# HARTShield.net
KiCad netlist of a schematic drawn in EAGLE
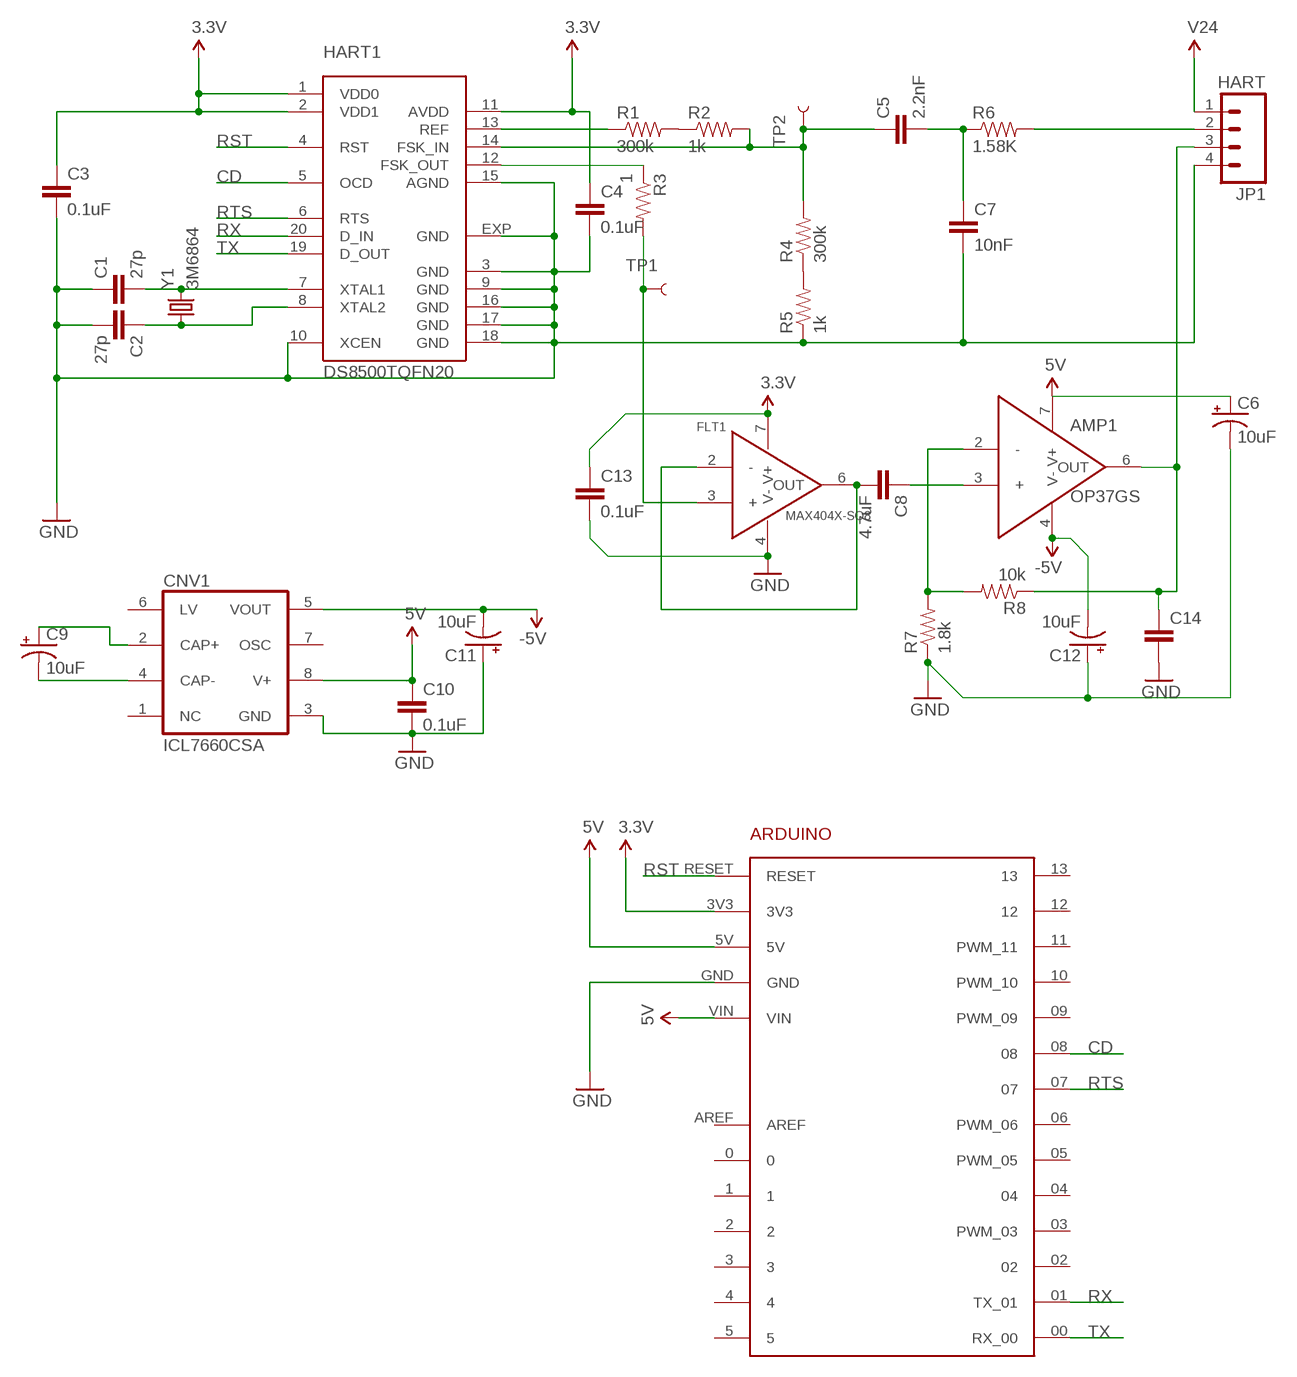
[diagram p0: schematic, sheet 1]

(export (version "E")
  (design (tool "Eeschema 10.0.6"))
  (components
    (comp (ref "AMP1")
      (value "OP37GS")
      (footprint "eagle-import:SO8")
      (libsource (lib "eagle-import") (part "OP37GS"))
    )
    (comp (ref "ARDUINO1")
      (value "ARDUINO")
      (footprint "eagle-import:ARDUINO")
      (libsource (lib "eagle-import") (part "ARDUINO"))
    )
    (comp (ref "C1")
      (value "27p")
      (footprint "eagle-import:0603-CAP")
      (libsource (lib "eagle-import") (part "CAP0603-CAP"))
    )
    (comp (ref "C2")
      (value "27p")
      (footprint "eagle-import:0603-CAP")
      (libsource (lib "eagle-import") (part "CAP0603-CAP"))
    )
    (comp (ref "C3")
      (value "0.1uF")
      (footprint "eagle-import:0603-CAP")
      (libsource (lib "eagle-import") (part "0.1UF-25V(+80/-20%)(0603)"))
    )
    (comp (ref "C4")
      (value "0.1uF")
      (footprint "eagle-import:0603-CAP")
      (libsource (lib "eagle-import") (part "0.1UF-25V(+80/-20%)(0603)"))
    )
    (comp (ref "C5")
      (value "2.2nF")
      (footprint "eagle-import:0603-CAP")
      (libsource (lib "eagle-import") (part "0.1UF-25V(+80/-20%)(0603)"))
    )
    (comp (ref "C6")
      (value "10uF")
      (footprint "eagle-import:EIA3216")
      (libsource (lib "eagle-import") (part "10UF-TANT"))
    )
    (comp (ref "C7")
      (value "10nF")
      (footprint "eagle-import:0603-CAP")
      (libsource (lib "eagle-import") (part "0.1UF-25V(+80/-20%)(0603)"))
    )
    (comp (ref "C8")
      (value "4.7uF")
      (footprint "eagle-import:0603-CAP")
      (libsource (lib "eagle-import") (part "0.1UF-25V(+80/-20%)(0603)"))
    )
    (comp (ref "C9")
      (value "10uF")
      (footprint "eagle-import:EIA3216")
      (libsource (lib "eagle-import") (part "10UF-TANT"))
    )
    (comp (ref "C10")
      (value "0.1uF")
      (footprint "eagle-import:0603-CAP")
      (libsource (lib "eagle-import") (part "0.1UF-25V(+80/-20%)(0603)"))
    )
    (comp (ref "C11")
      (value "10uF")
      (footprint "eagle-import:EIA3216")
      (libsource (lib "eagle-import") (part "10UF-TANT"))
    )
    (comp (ref "C12")
      (value "10uF")
      (footprint "eagle-import:EIA3216")
      (libsource (lib "eagle-import") (part "10UF-TANT"))
    )
    (comp (ref "C13")
      (value "0.1uF")
      (footprint "eagle-import:CAP-PTH-SMALL-KIT")
      (libsource (lib "eagle-import") (part "0.1UF-50V-20%(PTH)KIT-EZ"))
    )
    (comp (ref "C14")
      (value "0.1UF-50V-20%(PTH)KIT-EZ")
      (footprint "eagle-import:CAP-PTH-SMALL-KIT")
      (libsource (lib "eagle-import") (part "0.1UF-50V-20%(PTH)KIT-EZ"))
    )
    (comp (ref "CNV1")
      (value "ICL7660CSA")
      (footprint "eagle-import:SO08")
      (fields (field (name "MF") "MAXIM"))
      (libsource (lib "eagle-import") (part "ICL7660CSA"))
    )
    (comp (ref "FLT1")
      (value "MAX404X-SO8")
      (footprint "eagle-import:SO8")
      (libsource (lib "eagle-import") (part "MAX404X-SO8"))
    )
    (comp (ref "HART1")
      (value "DS8500TQFN20")
      (footprint "eagle-import:TQFN20-5X5")
      (libsource (lib "eagle-import") (part "DS8500TQFN20"))
    )
    (comp (ref "JP1")
      (value "HART")
      (footprint "eagle-import:SCREWTERMINAL-3.5MM-4")
      (libsource (lib "eagle-import") (part "M04SCREW"))
    )
    (comp (ref "R1")
      (value "300k")
      (footprint "eagle-import:0805")
      (libsource (lib "eagle-import") (part "RESISTOR0805-RES"))
    )
    (comp (ref "R2")
      (value "1k")
      (footprint "eagle-import:0805")
      (libsource (lib "eagle-import") (part "RESISTOR0805-RES"))
    )
    (comp (ref "R3")
      (value "1")
      (footprint "eagle-import:1206")
      (libsource (lib "eagle-import") (part "RESISTOR1206"))
    )
    (comp (ref "R4")
      (value "300k")
      (footprint "eagle-import:0805")
      (libsource (lib "eagle-import") (part "RESISTOR0805-RES"))
    )
    (comp (ref "R5")
      (value "1k")
      (footprint "eagle-import:0805")
      (libsource (lib "eagle-import") (part "RESISTOR0805-RES"))
    )
    (comp (ref "R6")
      (value "1.58K")
      (footprint "eagle-import:0603-RES")
      (libsource (lib "eagle-import") (part "RESISTOR0603"))
    )
    (comp (ref "R7")
      (value "1.8k")
      (footprint "eagle-import:0805")
      (libsource (lib "eagle-import") (part "RESISTOR0805-RES"))
    )
    (comp (ref "R8")
      (value "10k")
      (footprint "eagle-import:0805")
      (libsource (lib "eagle-import") (part "RESISTOR0805-RES"))
    )
    (comp (ref "TP1")
      (value "TEST-POINT2")
      (footprint "eagle-import:PAD.02X.02")
      (libsource (lib "eagle-import") (part "TEST-POINT2"))
    )
    (comp (ref "TP2")
      (value "TEST-POINT2")
      (footprint "eagle-import:PAD.02X.02")
      (libsource (lib "eagle-import") (part "TEST-POINT2"))
    )
    (comp (ref "Y1")
      (value "3M6864")
      (footprint "eagle-import:HC49UP")
      (libsource (lib "eagle-import") (part "CRYSTALSMD"))
    )
  )
  (nets
    (net (code "1") (name "-5V") (class "Default")
      (node (ref "AMP1") (pin "4") (pinfunction "V-_4") (pintype "bidirectional"))
      (node (ref "C11") (pin "C") (pinfunction "-_C") (pintype "passive"))
      (node (ref "C12") (pin "C") (pinfunction "-_C") (pintype "passive"))
      (node (ref "CNV1") (pin "5") (pinfunction "VOUT_5") (pintype "output"))
    )
    (net (code "2") (name "/CD") (class "Default")
      (node (ref "ARDUINO1") (pin "08") (pinfunction "08_08") (pintype "bidirectional"))
      (node (ref "HART1") (pin "5") (pinfunction "OCD_5") (pintype "bidirectional"))
    )
    (net (code "3") (name "/RST") (class "Default")
      (node (ref "ARDUINO1") (pin "RESET") (pinfunction "RESET_RESET") (pintype "bidirectional"))
      (node (ref "HART1") (pin "4") (pinfunction "RST_4") (pintype "bidirectional"))
    )
    (net (code "4") (name "/RTS") (class "Default")
      (node (ref "ARDUINO1") (pin "07") (pinfunction "07_07") (pintype "bidirectional"))
      (node (ref "HART1") (pin "6") (pinfunction "RTS_6") (pintype "bidirectional"))
    )
    (net (code "5") (name "/RX") (class "Default")
      (node (ref "ARDUINO1") (pin "01") (pinfunction "TX_01_01") (pintype "bidirectional"))
      (node (ref "HART1") (pin "20") (pinfunction "D_IN_20") (pintype "bidirectional"))
    )
    (net (code "6") (name "/TX") (class "Default")
      (node (ref "ARDUINO1") (pin "00") (pinfunction "RX_00_00") (pintype "bidirectional"))
      (node (ref "HART1") (pin "19") (pinfunction "D_OUT_19") (pintype "bidirectional"))
    )
    (net (code "7") (name "3.3V") (class "Default")
      (node (ref "ARDUINO1") (pin "3V3") (pinfunction "3V3_3V3") (pintype "bidirectional"))
      (node (ref "C13") (pin "1") (pinfunction "1_1") (pintype "passive"))
      (node (ref "C3") (pin "1") (pinfunction "1_1") (pintype "passive"))
      (node (ref "C4") (pin "1") (pinfunction "1_1") (pintype "passive"))
      (node (ref "FLT1") (pin "7") (pinfunction "V+_7") (pintype "bidirectional"))
      (node (ref "HART1") (pin "1") (pinfunction "VDD0_1") (pintype "bidirectional"))
      (node (ref "HART1") (pin "11") (pinfunction "AVDD_11") (pintype "bidirectional"))
      (node (ref "HART1") (pin "2") (pinfunction "VDD1_2") (pintype "bidirectional"))
    )
    (net (code "8") (name "5V") (class "Default")
      (node (ref "AMP1") (pin "7") (pinfunction "V+_7") (pintype "bidirectional"))
      (node (ref "ARDUINO1") (pin "5V") (pinfunction "5V_5V") (pintype "bidirectional"))
      (node (ref "ARDUINO1") (pin "VIN") (pinfunction "VIN_VIN") (pintype "bidirectional"))
      (node (ref "C10") (pin "1") (pinfunction "1_1") (pintype "passive"))
      (node (ref "C6") (pin "A") (pinfunction "+_A") (pintype "passive"))
      (node (ref "CNV1") (pin "8") (pinfunction "V+_8") (pintype "power_in"))
    )
    (net (code "9") (name "GND") (class "Default")
      (node (ref "ARDUINO1") (pin "GND") (pinfunction "GND_GND") (pintype "bidirectional"))
      (node (ref "C1") (pin "1") (pinfunction "1_1") (pintype "passive"))
      (node (ref "C10") (pin "2") (pinfunction "2_2") (pintype "passive"))
      (node (ref "C11") (pin "A") (pinfunction "+_A") (pintype "passive"))
      (node (ref "C12") (pin "A") (pinfunction "+_A") (pintype "passive"))
      (node (ref "C13") (pin "2") (pinfunction "2_2") (pintype "passive"))
      (node (ref "C14") (pin "2") (pinfunction "2_2") (pintype "passive"))
      (node (ref "C2") (pin "2") (pinfunction "2_2") (pintype "passive"))
      (node (ref "C3") (pin "2") (pinfunction "2_2") (pintype "passive"))
      (node (ref "C4") (pin "2") (pinfunction "2_2") (pintype "passive"))
      (node (ref "C6") (pin "C") (pinfunction "-_C") (pintype "passive"))
      (node (ref "C7") (pin "2") (pinfunction "2_2") (pintype "passive"))
      (node (ref "CNV1") (pin "3") (pinfunction "GND_3") (pintype "power_in"))
      (node (ref "FLT1") (pin "4") (pinfunction "V-_4") (pintype "bidirectional"))
      (node (ref "HART1") (pin "10") (pinfunction "XCEN_10") (pintype "bidirectional"))
      (node (ref "HART1") (pin "15") (pinfunction "AGND_15") (pintype "bidirectional"))
      (node (ref "HART1") (pin "16") (pinfunction "GND_16") (pintype "bidirectional"))
      (node (ref "HART1") (pin "17") (pinfunction "GND_17") (pintype "bidirectional"))
      (node (ref "HART1") (pin "18") (pinfunction "GND_18") (pintype "bidirectional"))
      (node (ref "HART1") (pin "3") (pinfunction "GND_3") (pintype "bidirectional"))
      (node (ref "HART1") (pin "9") (pinfunction "GND_9") (pintype "bidirectional"))
      (node (ref "HART1") (pin "EXP") (pinfunction "GND_EXP") (pintype "bidirectional"))
      (node (ref "JP1") (pin "4") (pinfunction "4_4") (pintype "passive"))
      (node (ref "R5") (pin "1") (pinfunction "1_1") (pintype "passive"))
      (node (ref "R7") (pin "1") (pinfunction "1_1") (pintype "passive"))
    )
    (net (code "10") (name "Net-(AMP1-+)") (class "Default")
      (node (ref "AMP1") (pin "3") (pinfunction "+_3") (pintype "bidirectional"))
      (node (ref "C8") (pin "1") (pinfunction "1_1") (pintype "passive"))
    )
    (net (code "11") (name "Net-(AMP1--)") (class "Default")
      (node (ref "AMP1") (pin "2") (pinfunction "-_2") (pintype "bidirectional"))
      (node (ref "R7") (pin "2") (pinfunction "2_2") (pintype "passive"))
      (node (ref "R8") (pin "2") (pinfunction "2_2") (pintype "passive"))
    )
    (net (code "12") (name "Net-(AMP1-OUT)") (class "Default")
      (node (ref "AMP1") (pin "6") (pinfunction "OUT_6") (pintype "bidirectional"))
      (node (ref "C14") (pin "1") (pinfunction "1_1") (pintype "passive"))
      (node (ref "JP1") (pin "3") (pinfunction "3_3") (pintype "passive"))
      (node (ref "R8") (pin "1") (pinfunction "1_1") (pintype "passive"))
    )
    (net (code "13") (name "Net-(C5-Pad2)") (class "Default")
      (node (ref "C5") (pin "2") (pinfunction "2_2") (pintype "passive"))
      (node (ref "C7") (pin "1") (pinfunction "1_1") (pintype "passive"))
      (node (ref "R6") (pin "1") (pinfunction "1_1") (pintype "passive"))
    )
    (net (code "14") (name "Net-(C9-+)") (class "Default")
      (node (ref "C9") (pin "A") (pinfunction "+_A") (pintype "passive"))
      (node (ref "CNV1") (pin "2") (pinfunction "CAP+_2") (pintype "passive"))
    )
    (net (code "15") (name "Net-(C9--)") (class "Default")
      (node (ref "C9") (pin "C") (pinfunction "-_C") (pintype "passive"))
      (node (ref "CNV1") (pin "4") (pinfunction "CAP-_4") (pintype "passive"))
    )
    (net (code "16") (name "Net-(FLT1-+)") (class "Default")
      (node (ref "FLT1") (pin "3") (pinfunction "+_3") (pintype "bidirectional"))
      (node (ref "R3") (pin "2") (pinfunction "2_2") (pintype "passive"))
      (node (ref "TP1") (pin "P$1") (pinfunction "1_P$1") (pintype "bidirectional"))
    )
    (net (code "17") (name "Net-(FLT1--)") (class "Default")
      (node (ref "C8") (pin "2") (pinfunction "2_2") (pintype "passive"))
      (node (ref "FLT1") (pin "2") (pinfunction "-_2") (pintype "bidirectional"))
      (node (ref "FLT1") (pin "6") (pinfunction "OUT_6") (pintype "bidirectional"))
    )
    (net (code "18") (name "Net-(HART1-FSK_IN)") (class "Default")
      (node (ref "C5") (pin "1") (pinfunction "1_1") (pintype "passive"))
      (node (ref "HART1") (pin "14") (pinfunction "FSK_IN_14") (pintype "bidirectional"))
      (node (ref "R2") (pin "2") (pinfunction "2_2") (pintype "passive"))
      (node (ref "R4") (pin "2") (pinfunction "2_2") (pintype "passive"))
      (node (ref "TP2") (pin "P$1") (pinfunction "1_P$1") (pintype "bidirectional"))
    )
    (net (code "19") (name "Net-(HART1-FSK_OUT)") (class "Default")
      (node (ref "HART1") (pin "12") (pinfunction "FSK_OUT_12") (pintype "bidirectional"))
      (node (ref "R3") (pin "1") (pinfunction "1_1") (pintype "passive"))
    )
    (net (code "20") (name "Net-(HART1-REF)") (class "Default")
      (node (ref "HART1") (pin "13") (pinfunction "REF_13") (pintype "bidirectional"))
      (node (ref "R1") (pin "1") (pinfunction "1_1") (pintype "passive"))
    )
    (net (code "21") (name "Net-(HART1-XTAL1)") (class "Default")
      (node (ref "C1") (pin "2") (pinfunction "2_2") (pintype "passive"))
      (node (ref "HART1") (pin "7") (pinfunction "XTAL1_7") (pintype "bidirectional"))
      (node (ref "Y1") (pin "2") (pinfunction "2_2") (pintype "passive"))
    )
    (net (code "22") (name "Net-(HART1-XTAL2)") (class "Default")
      (node (ref "C2") (pin "1") (pinfunction "1_1") (pintype "passive"))
      (node (ref "HART1") (pin "8") (pinfunction "XTAL2_8") (pintype "bidirectional"))
      (node (ref "Y1") (pin "1") (pinfunction "1_1") (pintype "passive"))
    )
    (net (code "23") (name "Net-(JP1-Pad2)") (class "Default")
      (node (ref "JP1") (pin "2") (pinfunction "2_2") (pintype "passive"))
      (node (ref "R6") (pin "2") (pinfunction "2_2") (pintype "passive"))
    )
    (net (code "24") (name "Net-(R1-Pad2)") (class "Default")
      (node (ref "R1") (pin "2") (pinfunction "2_2") (pintype "passive"))
      (node (ref "R2") (pin "1") (pinfunction "1_1") (pintype "passive"))
    )
    (net (code "25") (name "Net-(R4-Pad1)") (class "Default")
      (node (ref "R4") (pin "1") (pinfunction "1_1") (pintype "passive"))
      (node (ref "R5") (pin "2") (pinfunction "2_2") (pintype "passive"))
    )
    (net (code "26") (name "V24") (class "Default")
      (node (ref "JP1") (pin "1") (pinfunction "1_1") (pintype "passive"))
    )
    (net (code "27") (name "unconnected-(ARDUINO1-PWM_03-Pad03)") (class "Default")
      (node (ref "ARDUINO1") (pin "03") (pinfunction "PWM_03_03") (pintype "bidirectional"))
    )
    (net (code "28") (name "unconnected-(ARDUINO1-PWM_05-Pad05)") (class "Default")
      (node (ref "ARDUINO1") (pin "05") (pinfunction "PWM_05_05") (pintype "bidirectional"))
    )
    (net (code "29") (name "unconnected-(ARDUINO1-PWM_06-Pad06)") (class "Default")
      (node (ref "ARDUINO1") (pin "06") (pinfunction "PWM_06_06") (pintype "bidirectional"))
    )
    (net (code "30") (name "unconnected-(ARDUINO1-PWM_09-Pad09)") (class "Default")
      (node (ref "ARDUINO1") (pin "09") (pinfunction "PWM_09_09") (pintype "bidirectional"))
    )
    (net (code "31") (name "unconnected-(ARDUINO1-PWM_10-Pad10)") (class "Default")
      (node (ref "ARDUINO1") (pin "10") (pinfunction "PWM_10_10") (pintype "bidirectional"))
    )
    (net (code "32") (name "unconnected-(ARDUINO1-PWM_11-Pad11)") (class "Default")
      (node (ref "ARDUINO1") (pin "11") (pinfunction "PWM_11_11") (pintype "bidirectional"))
    )
    (net (code "33") (name "unconnected-(ARDUINO1-Pad0)") (class "Default")
      (node (ref "ARDUINO1") (pin "0") (pinfunction "0_0") (pintype "bidirectional"))
    )
    (net (code "34") (name "unconnected-(ARDUINO1-Pad1)") (class "Default")
      (node (ref "ARDUINO1") (pin "1") (pinfunction "1_1") (pintype "bidirectional"))
    )
    (net (code "35") (name "unconnected-(ARDUINO1-Pad02)") (class "Default")
      (node (ref "ARDUINO1") (pin "02") (pinfunction "02_02") (pintype "bidirectional"))
    )
    (net (code "36") (name "unconnected-(ARDUINO1-Pad2)") (class "Default")
      (node (ref "ARDUINO1") (pin "2") (pinfunction "2_2") (pintype "bidirectional"))
    )
    (net (code "37") (name "unconnected-(ARDUINO1-Pad3)") (class "Default")
      (node (ref "ARDUINO1") (pin "3") (pinfunction "3_3") (pintype "bidirectional"))
    )
    (net (code "38") (name "unconnected-(ARDUINO1-Pad4)") (class "Default")
      (node (ref "ARDUINO1") (pin "4") (pinfunction "4_4") (pintype "bidirectional"))
    )
    (net (code "39") (name "unconnected-(ARDUINO1-Pad04)") (class "Default")
      (node (ref "ARDUINO1") (pin "04") (pinfunction "04_04") (pintype "bidirectional"))
    )
    (net (code "40") (name "unconnected-(ARDUINO1-Pad5)") (class "Default")
      (node (ref "ARDUINO1") (pin "5") (pinfunction "5_5") (pintype "bidirectional"))
    )
    (net (code "41") (name "unconnected-(ARDUINO1-Pad12)") (class "Default")
      (node (ref "ARDUINO1") (pin "12") (pinfunction "12_12") (pintype "bidirectional"))
    )
    (net (code "42") (name "unconnected-(ARDUINO1-Pad13)") (class "Default")
      (node (ref "ARDUINO1") (pin "13") (pinfunction "13_13") (pintype "bidirectional"))
    )
    (net (code "43") (name "unconnected-(ARDUINO1-PadAREF)") (class "Default")
      (node (ref "ARDUINO1") (pin "AREF") (pinfunction "AREF_AREF") (pintype "bidirectional"))
    )
    (net (code "44") (name "unconnected-(CNV1-LV-Pad6)") (class "Default")
      (node (ref "CNV1") (pin "6") (pinfunction "LV_6") (pintype "passive"))
    )
    (net (code "45") (name "unconnected-(CNV1-NC-Pad1)") (class "Default")
      (node (ref "CNV1") (pin "1") (pinfunction "NC_1") (pintype "no_connect"))
    )
    (net (code "46") (name "unconnected-(CNV1-OSC-Pad7)") (class "Default")
      (node (ref "CNV1") (pin "7") (pinfunction "OSC_7") (pintype "output"))
    )
  )
)
